# FPGA-6.net
KiCad netlist of a schematic drawn in Altium Designer
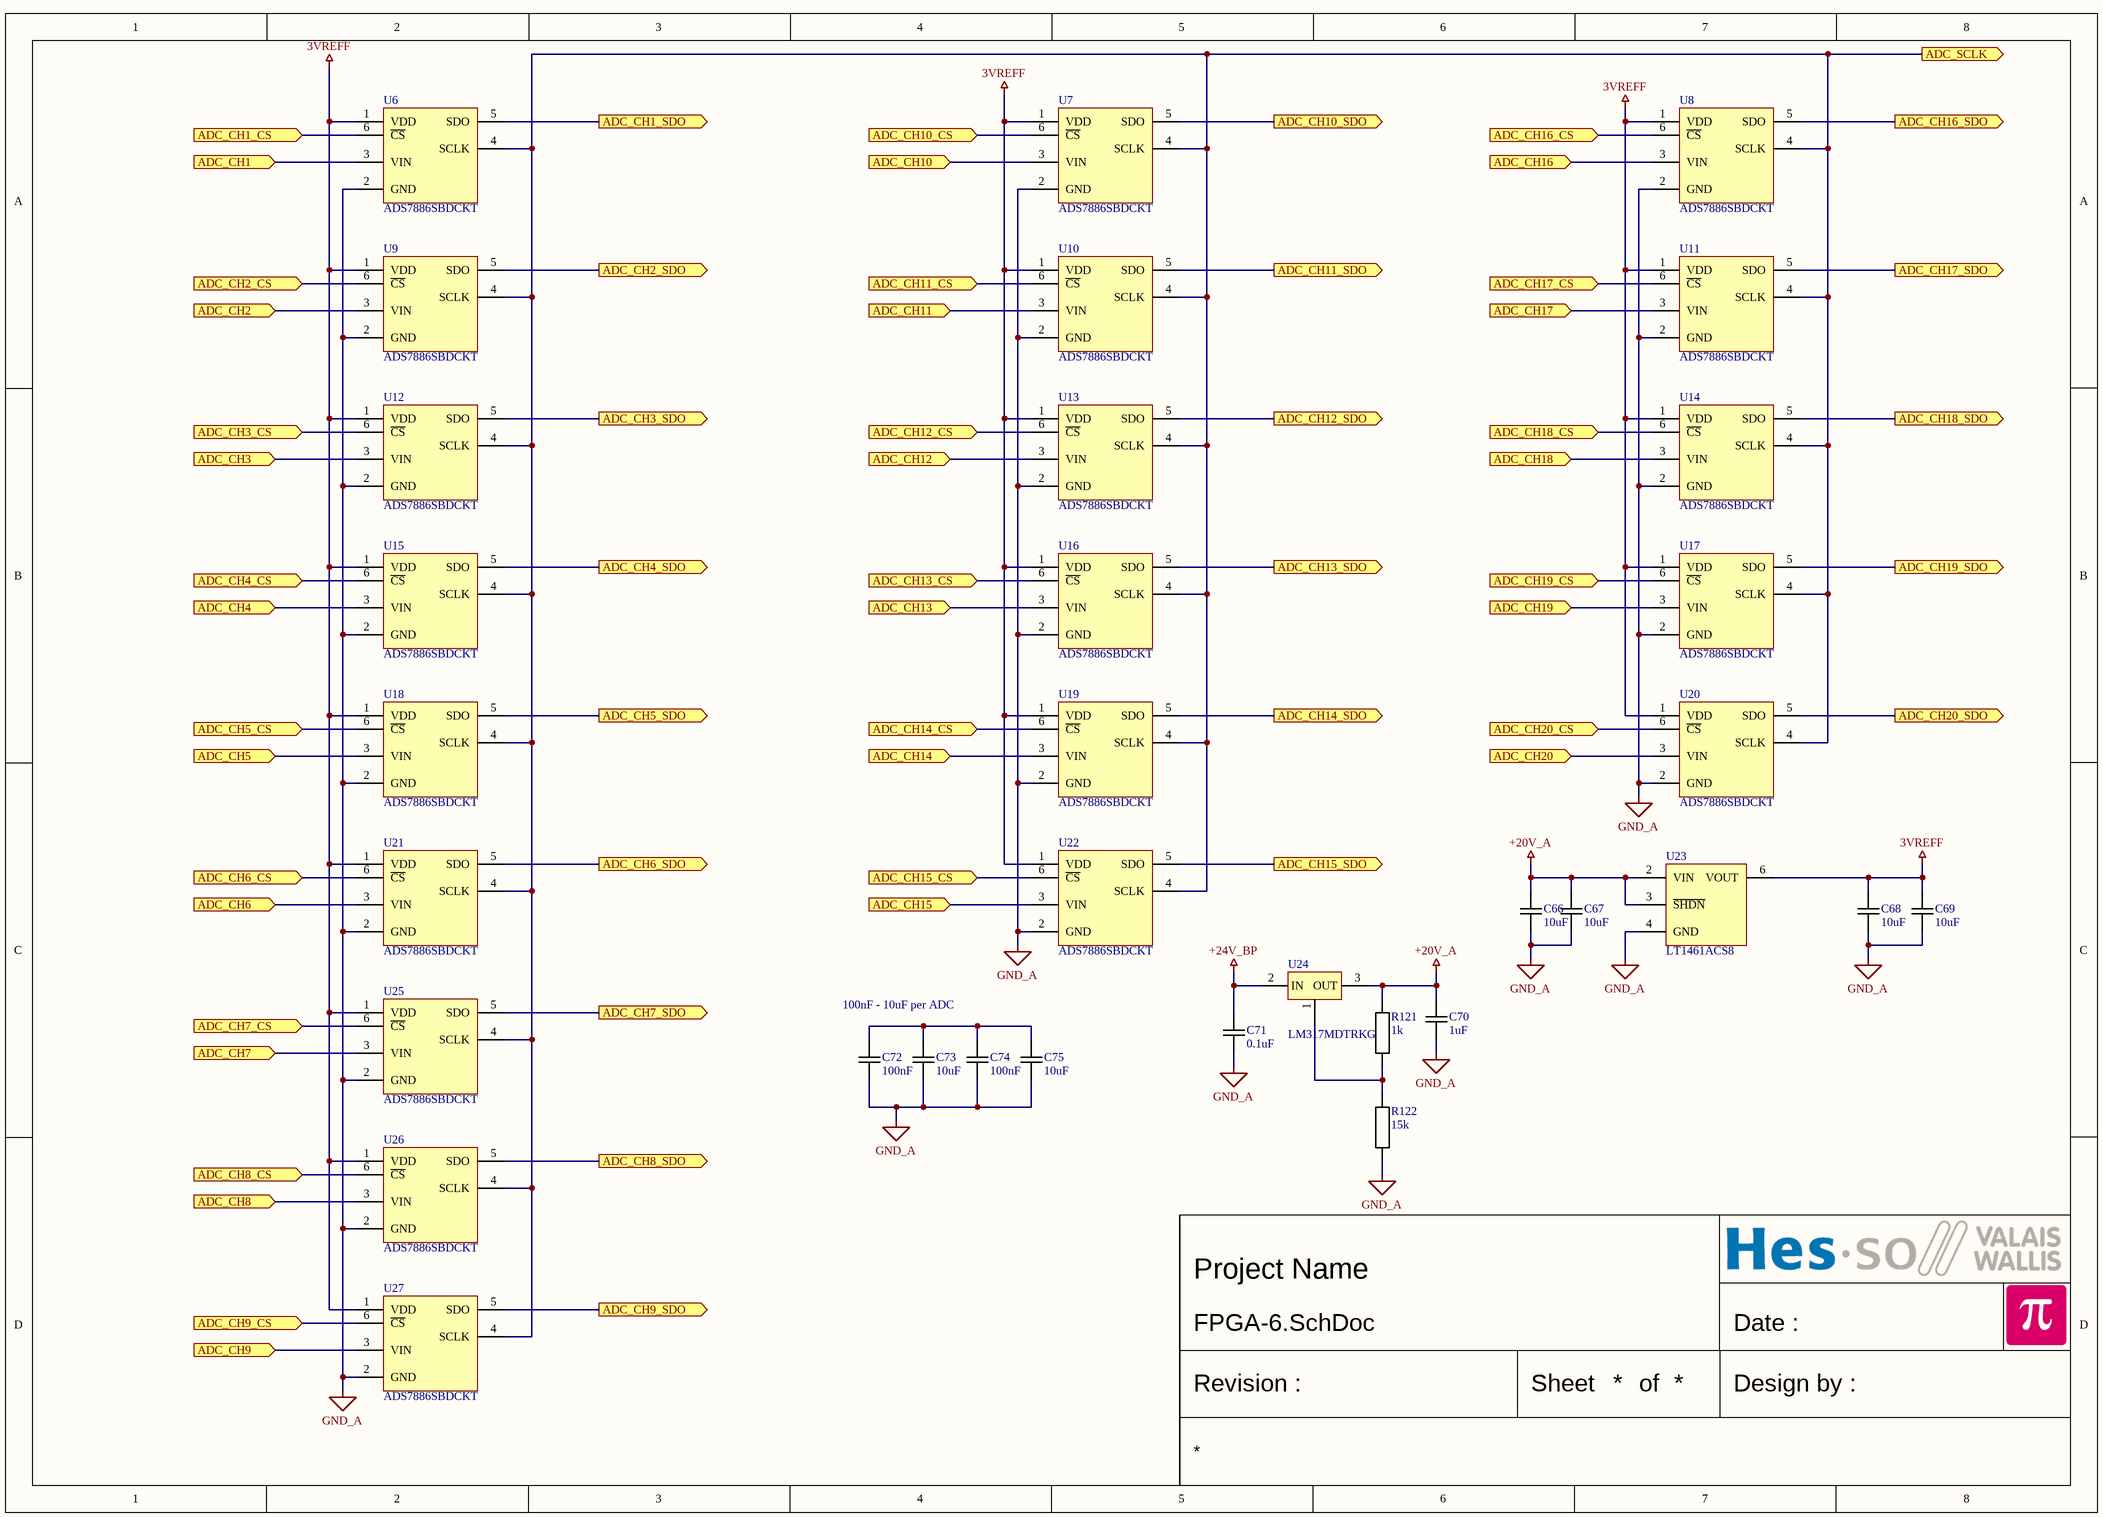
[diagram p0: FPGA-6.SchDoc]

(export (version "E")
  (design (tool "Eeschema 10.0.6"))
  (components
    (comp (ref "C66")
      (value "10uF")
      (footprint "CAPACITOR 1608 REFLOW")
      (description "Capacitor")
      (libsource (lib "Capacitor") (part "Capacitor"))
    )
    (comp (ref "C67")
      (value "10uF")
      (footprint "CAPACITOR 1608 REFLOW")
      (description "Capacitor")
      (libsource (lib "Capacitor") (part "Capacitor"))
    )
    (comp (ref "C68")
      (value "10uF")
      (footprint "CAPACITOR 1608 REFLOW")
      (description "Capacitor")
      (libsource (lib "Capacitor") (part "Capacitor"))
    )
    (comp (ref "C69")
      (value "10uF")
      (footprint "CAPACITOR 1608 REFLOW")
      (description "Capacitor")
      (libsource (lib "Capacitor") (part "Capacitor"))
    )
    (comp (ref "C70")
      (value "1uF")
      (footprint "CAPACITOR 1608 REFLOW")
      (description "Capacitor")
      (libsource (lib "Capacitor") (part "Capacitor"))
    )
    (comp (ref "C71")
      (value "0.1uF")
      (footprint "CAPACITOR 1608 REFLOW")
      (description "Capacitor")
      (libsource (lib "Capacitor") (part "Capacitor"))
    )
    (comp (ref "C72")
      (value "100nF")
      (footprint "CAPACITOR 1005 REFLOW")
      (description "Capacitor")
      (libsource (lib "Capacitor") (part "Capacitor"))
    )
    (comp (ref "C73")
      (value "10uF")
      (footprint "CAPACITOR 1608 REFLOW")
      (description "Capacitor")
      (libsource (lib "Capacitor") (part "Capacitor"))
    )
    (comp (ref "C74")
      (value "100nF")
      (footprint "CAPACITOR 1005 REFLOW")
      (description "Capacitor")
      (libsource (lib "Capacitor") (part "Capacitor"))
    )
    (comp (ref "C75")
      (value "10uF")
      (footprint "CAPACITOR 1608 REFLOW")
      (description "Capacitor")
      (libsource (lib "Capacitor") (part "Capacitor"))
    )
    (comp (ref "R121")
      (value "1k")
      (footprint "RESISTOR 1608 REFLOW")
      (description "Resistor 1% 50V 100mW 1608(0603)")
      (libsource (lib "Resistor") (part "Resistor"))
    )
    (comp (ref "R122")
      (value "15k")
      (footprint "RESISTOR 1608 REFLOW")
      (description "Resistor 1% 50V 100mW 1608(0603)")
      (libsource (lib "Resistor") (part "Resistor"))
    )
    (comp (ref "U6")
      (value "ADS7886SBDCKT")
      (footprint "SOT23-6 P0.95 C1.5x3.0 H1.3")
      (description "12-Bit, 1-MSPS, Micro-Power, Miniature SAR Analog-to-Digital Converters")
      (libsource (lib "Converter") (part "ADS7886SBDCKT"))
    )
    (comp (ref "U7")
      (value "ADS7886SBDCKT")
      (footprint "SOT23-6 P0.95 C1.5x3.0 H1.3")
      (description "12-Bit, 1-MSPS, Micro-Power, Miniature SAR Analog-to-Digital Converters")
      (libsource (lib "Converter") (part "ADS7886SBDCKT"))
    )
    (comp (ref "U8")
      (value "ADS7886SBDCKT")
      (footprint "SOT23-6 P0.95 C1.5x3.0 H1.3")
      (description "12-Bit, 1-MSPS, Micro-Power, Miniature SAR Analog-to-Digital Converters")
      (libsource (lib "Converter") (part "ADS7886SBDCKT"))
    )
    (comp (ref "U9")
      (value "ADS7886SBDCKT")
      (footprint "SOT23-6 P0.95 C1.5x3.0 H1.3")
      (description "12-Bit, 1-MSPS, Micro-Power, Miniature SAR Analog-to-Digital Converters")
      (libsource (lib "Converter") (part "ADS7886SBDCKT"))
    )
    (comp (ref "U10")
      (value "ADS7886SBDCKT")
      (footprint "SOT23-6 P0.95 C1.5x3.0 H1.3")
      (description "12-Bit, 1-MSPS, Micro-Power, Miniature SAR Analog-to-Digital Converters")
      (libsource (lib "Converter") (part "ADS7886SBDCKT"))
    )
    (comp (ref "U11")
      (value "ADS7886SBDCKT")
      (footprint "SOT23-6 P0.95 C1.5x3.0 H1.3")
      (description "12-Bit, 1-MSPS, Micro-Power, Miniature SAR Analog-to-Digital Converters")
      (libsource (lib "Converter") (part "ADS7886SBDCKT"))
    )
    (comp (ref "U12")
      (value "ADS7886SBDCKT")
      (footprint "SOT23-6 P0.95 C1.5x3.0 H1.3")
      (description "12-Bit, 1-MSPS, Micro-Power, Miniature SAR Analog-to-Digital Converters")
      (libsource (lib "Converter") (part "ADS7886SBDCKT"))
    )
    (comp (ref "U13")
      (value "ADS7886SBDCKT")
      (footprint "SOT23-6 P0.95 C1.5x3.0 H1.3")
      (description "12-Bit, 1-MSPS, Micro-Power, Miniature SAR Analog-to-Digital Converters")
      (libsource (lib "Converter") (part "ADS7886SBDCKT"))
    )
    (comp (ref "U14")
      (value "ADS7886SBDCKT")
      (footprint "SOT23-6 P0.95 C1.5x3.0 H1.3")
      (description "12-Bit, 1-MSPS, Micro-Power, Miniature SAR Analog-to-Digital Converters")
      (libsource (lib "Converter") (part "ADS7886SBDCKT"))
    )
    (comp (ref "U15")
      (value "ADS7886SBDCKT")
      (footprint "SOT23-6 P0.95 C1.5x3.0 H1.3")
      (description "12-Bit, 1-MSPS, Micro-Power, Miniature SAR Analog-to-Digital Converters")
      (libsource (lib "Converter") (part "ADS7886SBDCKT"))
    )
    (comp (ref "U16")
      (value "ADS7886SBDCKT")
      (footprint "SOT23-6 P0.95 C1.5x3.0 H1.3")
      (description "12-Bit, 1-MSPS, Micro-Power, Miniature SAR Analog-to-Digital Converters")
      (libsource (lib "Converter") (part "ADS7886SBDCKT"))
    )
    (comp (ref "U17")
      (value "ADS7886SBDCKT")
      (footprint "SOT23-6 P0.95 C1.5x3.0 H1.3")
      (description "12-Bit, 1-MSPS, Micro-Power, Miniature SAR Analog-to-Digital Converters")
      (libsource (lib "Converter") (part "ADS7886SBDCKT"))
    )
    (comp (ref "U18")
      (value "ADS7886SBDCKT")
      (footprint "SOT23-6 P0.95 C1.5x3.0 H1.3")
      (description "12-Bit, 1-MSPS, Micro-Power, Miniature SAR Analog-to-Digital Converters")
      (libsource (lib "Converter") (part "ADS7886SBDCKT"))
    )
    (comp (ref "U19")
      (value "ADS7886SBDCKT")
      (footprint "SOT23-6 P0.95 C1.5x3.0 H1.3")
      (description "12-Bit, 1-MSPS, Micro-Power, Miniature SAR Analog-to-Digital Converters")
      (libsource (lib "Converter") (part "ADS7886SBDCKT"))
    )
    (comp (ref "U20")
      (value "ADS7886SBDCKT")
      (footprint "SOT23-6 P0.95 C1.5x3.0 H1.3")
      (description "12-Bit, 1-MSPS, Micro-Power, Miniature SAR Analog-to-Digital Converters")
      (libsource (lib "Converter") (part "ADS7886SBDCKT"))
    )
    (comp (ref "U21")
      (value "ADS7886SBDCKT")
      (footprint "SOT23-6 P0.95 C1.5x3.0 H1.3")
      (description "12-Bit, 1-MSPS, Micro-Power, Miniature SAR Analog-to-Digital Converters")
      (libsource (lib "Converter") (part "ADS7886SBDCKT"))
    )
    (comp (ref "U22")
      (value "ADS7886SBDCKT")
      (footprint "SOT23-6 P0.95 C1.5x3.0 H1.3")
      (description "12-Bit, 1-MSPS, Micro-Power, Miniature SAR Analog-to-Digital Converters")
      (libsource (lib "Converter") (part "ADS7886SBDCKT"))
    )
    (comp (ref "U23")
      (value "LT1461ACS8")
      (footprint "SO8 P1.27 C4.0X5.0 H1.75")
      (description "Micropower Precision Low Dropout Series Voltage Reference Family")
      (libsource (lib "Regulator") (part "LT1461ACS8"))
    )
    (comp (ref "U24")
      (value "LM317MDTRKG")
      (footprint "TO252-2 P2.29 C6.2x6.7 H2.4")
      (description "Generic Positive Voltage Regulator")
      (libsource (lib "Regulator") (part "REGPOS TO252-2 GND,VIN,OUT"))
    )
    (comp (ref "U25")
      (value "ADS7886SBDCKT")
      (footprint "SOT23-6 P0.95 C1.5x3.0 H1.3")
      (description "12-Bit, 1-MSPS, Micro-Power, Miniature SAR Analog-to-Digital Converters")
      (libsource (lib "Converter") (part "ADS7886SBDCKT"))
    )
    (comp (ref "U26")
      (value "ADS7886SBDCKT")
      (footprint "SOT23-6 P0.95 C1.5x3.0 H1.3")
      (description "12-Bit, 1-MSPS, Micro-Power, Miniature SAR Analog-to-Digital Converters")
      (libsource (lib "Converter") (part "ADS7886SBDCKT"))
    )
    (comp (ref "U27")
      (value "ADS7886SBDCKT")
      (footprint "SOT23-6 P0.95 C1.5x3.0 H1.3")
      (description "12-Bit, 1-MSPS, Micro-Power, Miniature SAR Analog-to-Digital Converters")
      (libsource (lib "Converter") (part "ADS7886SBDCKT"))
    )
  )
  (nets
    (net (code "1") (name "+20V_A") (class "Default")
      (node (ref "C66") (pin "2") (pinfunction "2_2") (pintype "passive"))
      (node (ref "C67") (pin "2") (pinfunction "2_2") (pintype "passive"))
      (node (ref "C70") (pin "2") (pinfunction "2_2") (pintype "passive"))
      (node (ref "R121") (pin "2") (pinfunction "2_2") (pintype "passive"))
      (node (ref "U23") (pin "2") (pinfunction "VIN_2") (pintype "passive"))
      (node (ref "U23") (pin "3") (pinfunction "~{SHDN}_3") (pintype "passive"))
      (node (ref "U24") (pin "3") (pinfunction "OUT_3") (pintype "passive"))
    )
    (net (code "2") (name "+24V_BP") (class "Default")
      (node (ref "C71") (pin "2") (pinfunction "2_2") (pintype "passive"))
      (node (ref "U24") (pin "2") (pinfunction "IN_2") (pintype "passive"))
    )
    (net (code "3") (name "/ADC_CH1") (class "Default")
      (node (ref "U6") (pin "3") (pinfunction "VIN_3") (pintype "passive"))
    )
    (net (code "4") (name "/ADC_CH1_CS") (class "Default")
      (node (ref "U6") (pin "6") (pinfunction "~{CS}_6") (pintype "passive"))
    )
    (net (code "5") (name "/ADC_CH1_SDO") (class "Default")
      (node (ref "U6") (pin "5") (pinfunction "SDO_5") (pintype "passive"))
    )
    (net (code "6") (name "/ADC_CH2") (class "Default")
      (node (ref "U9") (pin "3") (pinfunction "VIN_3") (pintype "passive"))
    )
    (net (code "7") (name "/ADC_CH2_CS") (class "Default")
      (node (ref "U9") (pin "6") (pinfunction "~{CS}_6") (pintype "passive"))
    )
    (net (code "8") (name "/ADC_CH2_SDO") (class "Default")
      (node (ref "U9") (pin "5") (pinfunction "SDO_5") (pintype "passive"))
    )
    (net (code "9") (name "/ADC_CH3") (class "Default")
      (node (ref "U12") (pin "3") (pinfunction "VIN_3") (pintype "passive"))
    )
    (net (code "10") (name "/ADC_CH3_CS") (class "Default")
      (node (ref "U12") (pin "6") (pinfunction "~{CS}_6") (pintype "passive"))
    )
    (net (code "11") (name "/ADC_CH3_SDO") (class "Default")
      (node (ref "U12") (pin "5") (pinfunction "SDO_5") (pintype "passive"))
    )
    (net (code "12") (name "/ADC_CH4") (class "Default")
      (node (ref "U15") (pin "3") (pinfunction "VIN_3") (pintype "passive"))
    )
    (net (code "13") (name "/ADC_CH4_CS") (class "Default")
      (node (ref "U15") (pin "6") (pinfunction "~{CS}_6") (pintype "passive"))
    )
    (net (code "14") (name "/ADC_CH4_SDO") (class "Default")
      (node (ref "U15") (pin "5") (pinfunction "SDO_5") (pintype "passive"))
    )
    (net (code "15") (name "/ADC_CH5") (class "Default")
      (node (ref "U18") (pin "3") (pinfunction "VIN_3") (pintype "passive"))
    )
    (net (code "16") (name "/ADC_CH5_CS") (class "Default")
      (node (ref "U18") (pin "6") (pinfunction "~{CS}_6") (pintype "passive"))
    )
    (net (code "17") (name "/ADC_CH5_SDO") (class "Default")
      (node (ref "U18") (pin "5") (pinfunction "SDO_5") (pintype "passive"))
    )
    (net (code "18") (name "/ADC_CH6") (class "Default")
      (node (ref "U21") (pin "3") (pinfunction "VIN_3") (pintype "passive"))
    )
    (net (code "19") (name "/ADC_CH6_CS") (class "Default")
      (node (ref "U21") (pin "6") (pinfunction "~{CS}_6") (pintype "passive"))
    )
    (net (code "20") (name "/ADC_CH6_SDO") (class "Default")
      (node (ref "U21") (pin "5") (pinfunction "SDO_5") (pintype "passive"))
    )
    (net (code "21") (name "/ADC_CH7") (class "Default")
      (node (ref "U25") (pin "3") (pinfunction "VIN_3") (pintype "passive"))
    )
    (net (code "22") (name "/ADC_CH7_CS") (class "Default")
      (node (ref "U25") (pin "6") (pinfunction "~{CS}_6") (pintype "passive"))
    )
    (net (code "23") (name "/ADC_CH7_SDO") (class "Default")
      (node (ref "U25") (pin "5") (pinfunction "SDO_5") (pintype "passive"))
    )
    (net (code "24") (name "/ADC_CH8") (class "Default")
      (node (ref "U26") (pin "3") (pinfunction "VIN_3") (pintype "passive"))
    )
    (net (code "25") (name "/ADC_CH8_CS") (class "Default")
      (node (ref "U26") (pin "6") (pinfunction "~{CS}_6") (pintype "passive"))
    )
    (net (code "26") (name "/ADC_CH8_SDO") (class "Default")
      (node (ref "U26") (pin "5") (pinfunction "SDO_5") (pintype "passive"))
    )
    (net (code "27") (name "/ADC_CH9") (class "Default")
      (node (ref "U27") (pin "3") (pinfunction "VIN_3") (pintype "passive"))
    )
    (net (code "28") (name "/ADC_CH9_CS") (class "Default")
      (node (ref "U27") (pin "6") (pinfunction "~{CS}_6") (pintype "passive"))
    )
    (net (code "29") (name "/ADC_CH9_SDO") (class "Default")
      (node (ref "U27") (pin "5") (pinfunction "SDO_5") (pintype "passive"))
    )
    (net (code "30") (name "/ADC_CH10") (class "Default")
      (node (ref "U7") (pin "3") (pinfunction "VIN_3") (pintype "passive"))
    )
    (net (code "31") (name "/ADC_CH10_CS") (class "Default")
      (node (ref "U7") (pin "6") (pinfunction "~{CS}_6") (pintype "passive"))
    )
    (net (code "32") (name "/ADC_CH10_SDO") (class "Default")
      (node (ref "U7") (pin "5") (pinfunction "SDO_5") (pintype "passive"))
    )
    (net (code "33") (name "/ADC_CH11") (class "Default")
      (node (ref "U10") (pin "3") (pinfunction "VIN_3") (pintype "passive"))
    )
    (net (code "34") (name "/ADC_CH11_CS") (class "Default")
      (node (ref "U10") (pin "6") (pinfunction "~{CS}_6") (pintype "passive"))
    )
    (net (code "35") (name "/ADC_CH11_SDO") (class "Default")
      (node (ref "U10") (pin "5") (pinfunction "SDO_5") (pintype "passive"))
    )
    (net (code "36") (name "/ADC_CH12") (class "Default")
      (node (ref "U13") (pin "3") (pinfunction "VIN_3") (pintype "passive"))
    )
    (net (code "37") (name "/ADC_CH12_CS") (class "Default")
      (node (ref "U13") (pin "6") (pinfunction "~{CS}_6") (pintype "passive"))
    )
    (net (code "38") (name "/ADC_CH12_SDO") (class "Default")
      (node (ref "U13") (pin "5") (pinfunction "SDO_5") (pintype "passive"))
    )
    (net (code "39") (name "/ADC_CH13") (class "Default")
      (node (ref "U16") (pin "3") (pinfunction "VIN_3") (pintype "passive"))
    )
    (net (code "40") (name "/ADC_CH13_CS") (class "Default")
      (node (ref "U16") (pin "6") (pinfunction "~{CS}_6") (pintype "passive"))
    )
    (net (code "41") (name "/ADC_CH13_SDO") (class "Default")
      (node (ref "U16") (pin "5") (pinfunction "SDO_5") (pintype "passive"))
    )
    (net (code "42") (name "/ADC_CH14") (class "Default")
      (node (ref "U19") (pin "3") (pinfunction "VIN_3") (pintype "passive"))
    )
    (net (code "43") (name "/ADC_CH14_CS") (class "Default")
      (node (ref "U19") (pin "6") (pinfunction "~{CS}_6") (pintype "passive"))
    )
    (net (code "44") (name "/ADC_CH14_SDO") (class "Default")
      (node (ref "U19") (pin "5") (pinfunction "SDO_5") (pintype "passive"))
    )
    (net (code "45") (name "/ADC_CH15") (class "Default")
      (node (ref "U22") (pin "3") (pinfunction "VIN_3") (pintype "passive"))
    )
    (net (code "46") (name "/ADC_CH15_CS") (class "Default")
      (node (ref "U22") (pin "6") (pinfunction "~{CS}_6") (pintype "passive"))
    )
    (net (code "47") (name "/ADC_CH15_SDO") (class "Default")
      (node (ref "U22") (pin "5") (pinfunction "SDO_5") (pintype "passive"))
    )
    (net (code "48") (name "/ADC_CH16") (class "Default")
      (node (ref "U8") (pin "3") (pinfunction "VIN_3") (pintype "passive"))
    )
    (net (code "49") (name "/ADC_CH16_CS") (class "Default")
      (node (ref "U8") (pin "6") (pinfunction "~{CS}_6") (pintype "passive"))
    )
    (net (code "50") (name "/ADC_CH16_SDO") (class "Default")
      (node (ref "U8") (pin "5") (pinfunction "SDO_5") (pintype "passive"))
    )
    (net (code "51") (name "/ADC_CH17") (class "Default")
      (node (ref "U11") (pin "3") (pinfunction "VIN_3") (pintype "passive"))
    )
    (net (code "52") (name "/ADC_CH17_CS") (class "Default")
      (node (ref "U11") (pin "6") (pinfunction "~{CS}_6") (pintype "passive"))
    )
    (net (code "53") (name "/ADC_CH17_SDO") (class "Default")
      (node (ref "U11") (pin "5") (pinfunction "SDO_5") (pintype "passive"))
    )
    (net (code "54") (name "/ADC_CH18") (class "Default")
      (node (ref "U14") (pin "3") (pinfunction "VIN_3") (pintype "passive"))
    )
    (net (code "55") (name "/ADC_CH18_CS") (class "Default")
      (node (ref "U14") (pin "6") (pinfunction "~{CS}_6") (pintype "passive"))
    )
    (net (code "56") (name "/ADC_CH18_SDO") (class "Default")
      (node (ref "U14") (pin "5") (pinfunction "SDO_5") (pintype "passive"))
    )
    (net (code "57") (name "/ADC_CH19") (class "Default")
      (node (ref "U17") (pin "3") (pinfunction "VIN_3") (pintype "passive"))
    )
    (net (code "58") (name "/ADC_CH19_CS") (class "Default")
      (node (ref "U17") (pin "6") (pinfunction "~{CS}_6") (pintype "passive"))
    )
    (net (code "59") (name "/ADC_CH19_SDO") (class "Default")
      (node (ref "U17") (pin "5") (pinfunction "SDO_5") (pintype "passive"))
    )
    (net (code "60") (name "/ADC_CH20") (class "Default")
      (node (ref "U20") (pin "3") (pinfunction "VIN_3") (pintype "passive"))
    )
    (net (code "61") (name "/ADC_CH20_CS") (class "Default")
      (node (ref "U20") (pin "6") (pinfunction "~{CS}_6") (pintype "passive"))
    )
    (net (code "62") (name "/ADC_CH20_SDO") (class "Default")
      (node (ref "U20") (pin "5") (pinfunction "SDO_5") (pintype "passive"))
    )
    (net (code "63") (name "/ADC_SCLK") (class "Default")
      (node (ref "U10") (pin "4") (pinfunction "SCLK_4") (pintype "passive"))
      (node (ref "U11") (pin "4") (pinfunction "SCLK_4") (pintype "passive"))
      (node (ref "U12") (pin "4") (pinfunction "SCLK_4") (pintype "passive"))
      (node (ref "U13") (pin "4") (pinfunction "SCLK_4") (pintype "passive"))
      (node (ref "U14") (pin "4") (pinfunction "SCLK_4") (pintype "passive"))
      (node (ref "U15") (pin "4") (pinfunction "SCLK_4") (pintype "passive"))
      (node (ref "U16") (pin "4") (pinfunction "SCLK_4") (pintype "passive"))
      (node (ref "U17") (pin "4") (pinfunction "SCLK_4") (pintype "passive"))
      (node (ref "U18") (pin "4") (pinfunction "SCLK_4") (pintype "passive"))
      (node (ref "U19") (pin "4") (pinfunction "SCLK_4") (pintype "passive"))
      (node (ref "U20") (pin "4") (pinfunction "SCLK_4") (pintype "passive"))
      (node (ref "U21") (pin "4") (pinfunction "SCLK_4") (pintype "passive"))
      (node (ref "U22") (pin "4") (pinfunction "SCLK_4") (pintype "passive"))
      (node (ref "U25") (pin "4") (pinfunction "SCLK_4") (pintype "passive"))
      (node (ref "U26") (pin "4") (pinfunction "SCLK_4") (pintype "passive"))
      (node (ref "U27") (pin "4") (pinfunction "SCLK_4") (pintype "passive"))
      (node (ref "U6") (pin "4") (pinfunction "SCLK_4") (pintype "passive"))
      (node (ref "U7") (pin "4") (pinfunction "SCLK_4") (pintype "passive"))
      (node (ref "U8") (pin "4") (pinfunction "SCLK_4") (pintype "passive"))
      (node (ref "U9") (pin "4") (pinfunction "SCLK_4") (pintype "passive"))
    )
    (net (code "64") (name "3VREFF") (class "Default")
      (node (ref "C68") (pin "2") (pinfunction "2_2") (pintype "passive"))
      (node (ref "C69") (pin "2") (pinfunction "2_2") (pintype "passive"))
      (node (ref "U10") (pin "1") (pinfunction "VDD_1") (pintype "passive"))
      (node (ref "U11") (pin "1") (pinfunction "VDD_1") (pintype "passive"))
      (node (ref "U12") (pin "1") (pinfunction "VDD_1") (pintype "passive"))
      (node (ref "U13") (pin "1") (pinfunction "VDD_1") (pintype "passive"))
      (node (ref "U14") (pin "1") (pinfunction "VDD_1") (pintype "passive"))
      (node (ref "U15") (pin "1") (pinfunction "VDD_1") (pintype "passive"))
      (node (ref "U16") (pin "1") (pinfunction "VDD_1") (pintype "passive"))
      (node (ref "U17") (pin "1") (pinfunction "VDD_1") (pintype "passive"))
      (node (ref "U18") (pin "1") (pinfunction "VDD_1") (pintype "passive"))
      (node (ref "U19") (pin "1") (pinfunction "VDD_1") (pintype "passive"))
      (node (ref "U20") (pin "1") (pinfunction "VDD_1") (pintype "passive"))
      (node (ref "U21") (pin "1") (pinfunction "VDD_1") (pintype "passive"))
      (node (ref "U22") (pin "1") (pinfunction "VDD_1") (pintype "passive"))
      (node (ref "U23") (pin "6") (pinfunction "VOUT_6") (pintype "passive"))
      (node (ref "U25") (pin "1") (pinfunction "VDD_1") (pintype "passive"))
      (node (ref "U26") (pin "1") (pinfunction "VDD_1") (pintype "passive"))
      (node (ref "U27") (pin "1") (pinfunction "VDD_1") (pintype "passive"))
      (node (ref "U6") (pin "1") (pinfunction "VDD_1") (pintype "passive"))
      (node (ref "U7") (pin "1") (pinfunction "VDD_1") (pintype "passive"))
      (node (ref "U8") (pin "1") (pinfunction "VDD_1") (pintype "passive"))
      (node (ref "U9") (pin "1") (pinfunction "VDD_1") (pintype "passive"))
    )
    (net (code "65") (name "GND_A") (class "Default")
      (node (ref "C66") (pin "1") (pinfunction "1_1") (pintype "passive"))
      (node (ref "C67") (pin "1") (pinfunction "1_1") (pintype "passive"))
      (node (ref "C68") (pin "1") (pinfunction "1_1") (pintype "passive"))
      (node (ref "C69") (pin "1") (pinfunction "1_1") (pintype "passive"))
      (node (ref "C70") (pin "1") (pinfunction "1_1") (pintype "passive"))
      (node (ref "C71") (pin "1") (pinfunction "1_1") (pintype "passive"))
      (node (ref "C72") (pin "2") (pinfunction "2_2") (pintype "passive"))
      (node (ref "C73") (pin "2") (pinfunction "2_2") (pintype "passive"))
      (node (ref "C74") (pin "2") (pinfunction "2_2") (pintype "passive"))
      (node (ref "C75") (pin "2") (pinfunction "2_2") (pintype "passive"))
      (node (ref "R122") (pin "1") (pinfunction "1_1") (pintype "passive"))
      (node (ref "U10") (pin "2") (pinfunction "GND_2") (pintype "passive"))
      (node (ref "U11") (pin "2") (pinfunction "GND_2") (pintype "passive"))
      (node (ref "U12") (pin "2") (pinfunction "GND_2") (pintype "passive"))
      (node (ref "U13") (pin "2") (pinfunction "GND_2") (pintype "passive"))
      (node (ref "U14") (pin "2") (pinfunction "GND_2") (pintype "passive"))
      (node (ref "U15") (pin "2") (pinfunction "GND_2") (pintype "passive"))
      (node (ref "U16") (pin "2") (pinfunction "GND_2") (pintype "passive"))
      (node (ref "U17") (pin "2") (pinfunction "GND_2") (pintype "passive"))
      (node (ref "U18") (pin "2") (pinfunction "GND_2") (pintype "passive"))
      (node (ref "U19") (pin "2") (pinfunction "GND_2") (pintype "passive"))
      (node (ref "U20") (pin "2") (pinfunction "GND_2") (pintype "passive"))
      (node (ref "U21") (pin "2") (pinfunction "GND_2") (pintype "passive"))
      (node (ref "U22") (pin "2") (pinfunction "GND_2") (pintype "passive"))
      (node (ref "U23") (pin "4") (pinfunction "GND_4") (pintype "passive"))
      (node (ref "U25") (pin "2") (pinfunction "GND_2") (pintype "passive"))
      (node (ref "U26") (pin "2") (pinfunction "GND_2") (pintype "passive"))
      (node (ref "U27") (pin "2") (pinfunction "GND_2") (pintype "passive"))
      (node (ref "U6") (pin "2") (pinfunction "GND_2") (pintype "passive"))
      (node (ref "U7") (pin "2") (pinfunction "GND_2") (pintype "passive"))
      (node (ref "U8") (pin "2") (pinfunction "GND_2") (pintype "passive"))
      (node (ref "U9") (pin "2") (pinfunction "GND_2") (pintype "passive"))
    )
    (net (code "66") (name "Net-(C72-Pad1)") (class "Default")
      (node (ref "C72") (pin "1") (pinfunction "1_1") (pintype "passive"))
      (node (ref "C73") (pin "1") (pinfunction "1_1") (pintype "passive"))
      (node (ref "C74") (pin "1") (pinfunction "1_1") (pintype "passive"))
      (node (ref "C75") (pin "1") (pinfunction "1_1") (pintype "passive"))
    )
    (net (code "67") (name "Net-(U24-GND)") (class "Default")
      (node (ref "R121") (pin "1") (pinfunction "1_1") (pintype "passive"))
      (node (ref "R122") (pin "2") (pinfunction "2_2") (pintype "passive"))
      (node (ref "U24") (pin "1") (pinfunction "GND_1") (pintype "passive"))
    )
  )
)
